# Ambiente_superior.net
KiCad netlist of a schematic drawn in EAGLE
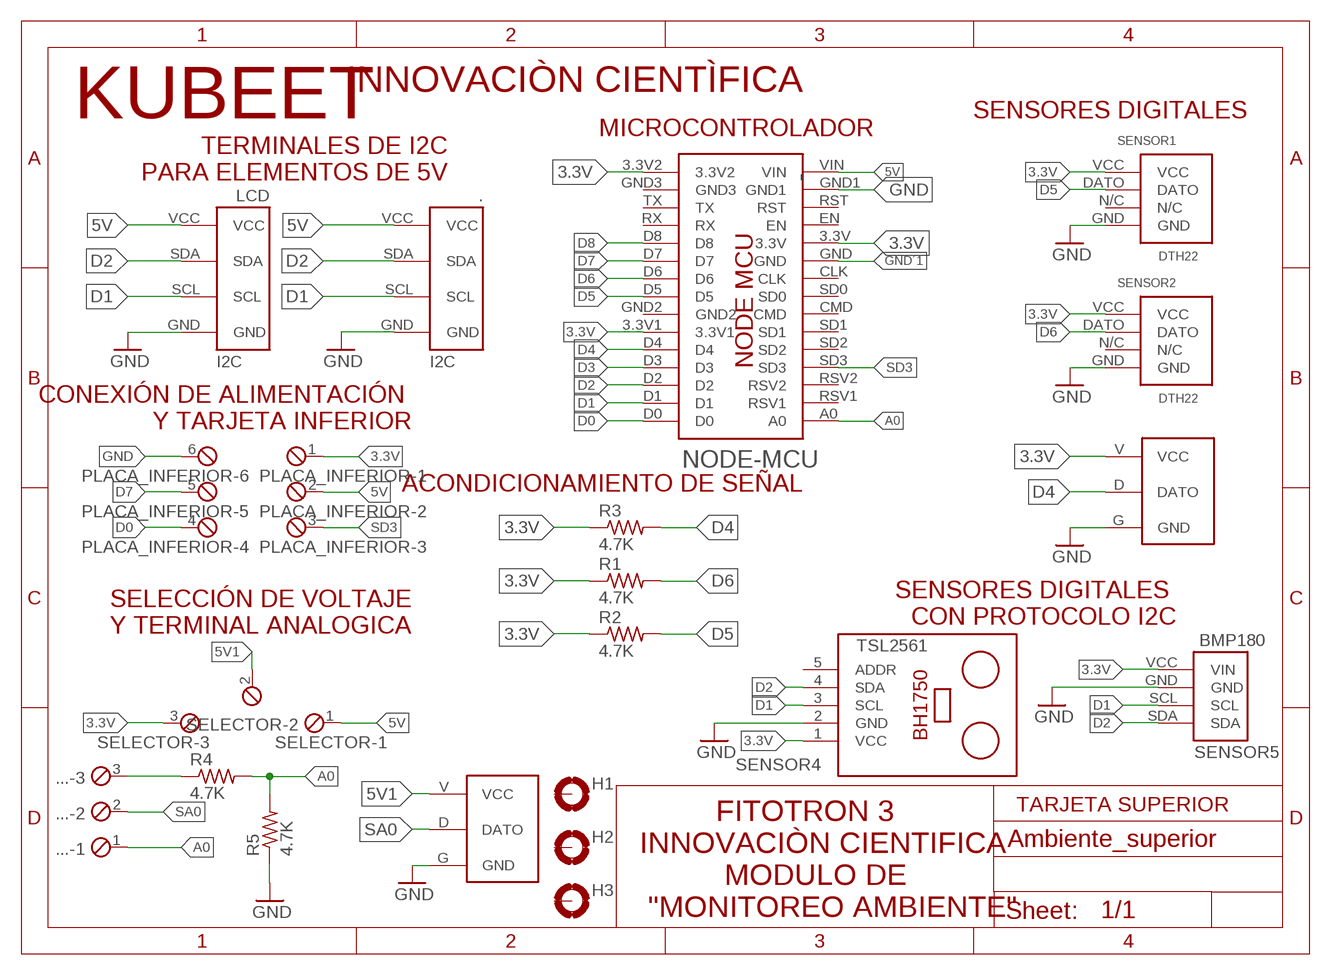
[diagram p0: schematic, sheet 1]

(export (version "E")
  (design (tool "Eeschema 10.0.6"))
  (components
    (comp (ref "-")
      (value "NODE-MCU")
      (footprint "eagle-import:NODE-MCU")
      (libsource (lib "eagle-import") (part "NODE-MCU"))
    )
    (comp (ref ".")
      (value "I2C")
      (footprint "eagle-import:I2C")
      (libsource (lib "eagle-import") (part "I2C"))
    )
    (comp (ref "..")
      (value "LM35")
      (footprint "eagle-import:LM35")
      (libsource (lib "eagle-import") (part "LM35"))
    )
    (comp (ref "...")
      (value "MPT3")
      (footprint "eagle-import:3POL254")
      (libsource (lib "eagle-import") (part "MPT3"))
    )
    (comp (ref "H1")
      (value "MOUNT-PAD-ROUND3.6")
      (footprint "eagle-import:3,6-PAD")
      (libsource (lib "eagle-import") (part "MOUNT-PAD-ROUND3.6"))
    )
    (comp (ref "H2")
      (value "MOUNT-PAD-ROUND3.6")
      (footprint "eagle-import:3,6-PAD")
      (libsource (lib "eagle-import") (part "MOUNT-PAD-ROUND3.6"))
    )
    (comp (ref "H3")
      (value "MOUNT-PAD-ROUND3.6")
      (footprint "eagle-import:3,6-PAD")
      (libsource (lib "eagle-import") (part "MOUNT-PAD-ROUND3.6"))
    )
    (comp (ref "LCD")
      (value "I2C")
      (footprint "eagle-import:I2C")
      (libsource (lib "eagle-import") (part "I2C"))
    )
    (comp (ref "PLACA_INFERIOR")
      (value "MPT6")
      (footprint "eagle-import:6POL254")
      (libsource (lib "eagle-import") (part "MPT6"))
    )
    (comp (ref "R1")
      (value "4.7K")
      (footprint "eagle-import:0207_7")
      (libsource (lib "eagle-import") (part "R-US_0207/7"))
    )
    (comp (ref "R2")
      (value "4.7K")
      (footprint "eagle-import:0207_7")
      (libsource (lib "eagle-import") (part "R-US_0207/7"))
    )
    (comp (ref "R3")
      (value "4.7K")
      (footprint "eagle-import:0207_7")
      (libsource (lib "eagle-import") (part "R-US_0207/7"))
    )
    (comp (ref "R4")
      (value "4.7K")
      (footprint "eagle-import:0207_7")
      (libsource (lib "eagle-import") (part "R-US_0207/7"))
    )
    (comp (ref "R5")
      (value "4.7K")
      (footprint "eagle-import:0207_7")
      (libsource (lib "eagle-import") (part "R-US_0207/7"))
    )
    (comp (ref "SELECTOR")
      (value "MPT3")
      (footprint "eagle-import:3POL254")
      (libsource (lib "eagle-import") (part "MPT3"))
    )
    (comp (ref "SENSOR1")
      (value "DTH22")
      (footprint "eagle-import:DTH22")
      (libsource (lib "eagle-import") (part "DTH22"))
    )
    (comp (ref "SENSOR2")
      (value "DTH22")
      (footprint "eagle-import:DTH22")
      (libsource (lib "eagle-import") (part "DTH22"))
    )
    (comp (ref "SENSOR3")
      (value "DS18B20")
      (footprint "eagle-import:LM35")
      (libsource (lib "eagle-import") (part "LM35"))
    )
    (comp (ref "SENSOR4")
      (value "TSL2561")
      (footprint "eagle-import:LIGHT-SENSOR-BH1750")
      (libsource (lib "eagle-import") (part "LIGHT-SENSOR-BH1750"))
    )
    (comp (ref "SENSOR5")
      (value "BMP180")
      (footprint "eagle-import:BMP180")
      (libsource (lib "eagle-import") (part "BMP180"))
    )
  )
  (nets
    (net (code "1") (name "3.3V") (class "Default")
      (node (ref "-") (pin "3.3V") (pinfunction "3.3V_3.3V") (pintype "bidirectional"))
      (node (ref "-") (pin "3.3V1") (pinfunction "3.3V1_3.3V1") (pintype "bidirectional"))
      (node (ref "-") (pin "3.3V2") (pinfunction "3.3V2_3.3V2") (pintype "bidirectional"))
      (node (ref "PLACA_INFERIOR") (pin "1") (pinfunction "1_1") (pintype "passive"))
      (node (ref "R1") (pin "1") (pinfunction "1_1") (pintype "passive"))
      (node (ref "R2") (pin "1") (pinfunction "1_1") (pintype "passive"))
      (node (ref "R3") (pin "1") (pinfunction "1_1") (pintype "passive"))
      (node (ref "SELECTOR") (pin "3") (pinfunction "1_3") (pintype "passive"))
      (node (ref "SENSOR1") (pin "VCC") (pinfunction "VCC_VCC") (pintype "bidirectional"))
      (node (ref "SENSOR2") (pin "VCC") (pinfunction "VCC_VCC") (pintype "bidirectional"))
      (node (ref "SENSOR3") (pin "V") (pinfunction "VCC_V") (pintype "bidirectional"))
      (node (ref "SENSOR4") (pin "1") (pinfunction "VCC_1") (pintype "power_in"))
      (node (ref "SENSOR5") (pin "VCC") (pinfunction "VIN_VCC") (pintype "bidirectional"))
    )
    (net (code "2") (name "5V") (class "Default")
      (node (ref "-") (pin "VIN") (pinfunction "VIN_VIN") (pintype "bidirectional"))
      (node (ref ".") (pin "VCC") (pinfunction "VCC_VCC") (pintype "bidirectional"))
      (node (ref "LCD") (pin "VCC") (pinfunction "VCC_VCC") (pintype "bidirectional"))
      (node (ref "PLACA_INFERIOR") (pin "2") (pinfunction "1_2") (pintype "passive"))
      (node (ref "SELECTOR") (pin "1") (pinfunction "1_1") (pintype "passive"))
    )
    (net (code "3") (name "5V1") (class "Default")
      (node (ref "..") (pin "V") (pinfunction "VCC_V") (pintype "bidirectional"))
      (node (ref "SELECTOR") (pin "2") (pinfunction "1_2") (pintype "passive"))
    )
    (net (code "4") (name "A0") (class "Default")
      (node (ref "-") (pin "A0") (pinfunction "A0_A0") (pintype "bidirectional"))
      (node (ref "...") (pin "1") (pinfunction "1_1") (pintype "passive"))
      (node (ref "R4") (pin "2") (pinfunction "2_2") (pintype "passive"))
      (node (ref "R5") (pin "2") (pinfunction "2_2") (pintype "passive"))
    )
    (net (code "5") (name "D0") (class "Default")
      (node (ref "-") (pin "D0") (pinfunction "D0_D0") (pintype "bidirectional"))
      (node (ref "PLACA_INFERIOR") (pin "4") (pinfunction "1_4") (pintype "passive"))
    )
    (net (code "6") (name "D1") (class "Default")
      (node (ref "-") (pin "D1") (pinfunction "D1_D1") (pintype "bidirectional"))
      (node (ref ".") (pin "SCL") (pinfunction "SCL_SCL") (pintype "bidirectional"))
      (node (ref "LCD") (pin "SCL") (pinfunction "SCL_SCL") (pintype "bidirectional"))
      (node (ref "SENSOR4") (pin "3") (pinfunction "SCL_3") (pintype "bidirectional"))
      (node (ref "SENSOR5") (pin "SCL") (pinfunction "SCL_SCL") (pintype "bidirectional"))
    )
    (net (code "7") (name "D2") (class "Default")
      (node (ref "-") (pin "D2") (pinfunction "D2_D2") (pintype "bidirectional"))
      (node (ref ".") (pin "SDA") (pinfunction "SDA_SDA") (pintype "bidirectional"))
      (node (ref "LCD") (pin "SDA") (pinfunction "SDA_SDA") (pintype "bidirectional"))
      (node (ref "SENSOR4") (pin "4") (pinfunction "SDA_4") (pintype "bidirectional"))
      (node (ref "SENSOR5") (pin "SDA") (pinfunction "SDA_SDA") (pintype "bidirectional"))
    )
    (net (code "8") (name "D3") (class "Default")
      (node (ref "-") (pin "D3") (pinfunction "D3_D3") (pintype "bidirectional"))
    )
    (net (code "9") (name "D4") (class "Default")
      (node (ref "-") (pin "D4") (pinfunction "D4_D4") (pintype "bidirectional"))
      (node (ref "R3") (pin "2") (pinfunction "2_2") (pintype "passive"))
      (node (ref "SENSOR3") (pin "D") (pinfunction "DATO_D") (pintype "bidirectional"))
    )
    (net (code "10") (name "D5") (class "Default")
      (node (ref "-") (pin "D5") (pinfunction "D5_D5") (pintype "bidirectional"))
      (node (ref "R2") (pin "2") (pinfunction "2_2") (pintype "passive"))
      (node (ref "SENSOR1") (pin "DATO") (pinfunction "DATO_DATO") (pintype "bidirectional"))
    )
    (net (code "11") (name "D6") (class "Default")
      (node (ref "-") (pin "D6") (pinfunction "D6_D6") (pintype "bidirectional"))
      (node (ref "R1") (pin "2") (pinfunction "2_2") (pintype "passive"))
      (node (ref "SENSOR2") (pin "DATO") (pinfunction "DATO_DATO") (pintype "bidirectional"))
    )
    (net (code "12") (name "D7") (class "Default")
      (node (ref "-") (pin "D7") (pinfunction "D7_D7") (pintype "bidirectional"))
      (node (ref "PLACA_INFERIOR") (pin "5") (pinfunction "1_5") (pintype "passive"))
    )
    (net (code "13") (name "D8") (class "Default")
      (node (ref "-") (pin "D8") (pinfunction "D8_D8") (pintype "bidirectional"))
    )
    (net (code "14") (name "GND") (class "Default")
      (node (ref "-") (pin "GND1") (pinfunction "GND1_GND1") (pintype "bidirectional"))
      (node (ref ".") (pin "GND") (pinfunction "GND_GND") (pintype "bidirectional"))
      (node (ref "..") (pin "G") (pinfunction "GND_G") (pintype "bidirectional"))
      (node (ref "LCD") (pin "GND") (pinfunction "GND_GND") (pintype "bidirectional"))
      (node (ref "PLACA_INFERIOR") (pin "6") (pinfunction "1_6") (pintype "passive"))
      (node (ref "R5") (pin "1") (pinfunction "1_1") (pintype "passive"))
      (node (ref "SENSOR1") (pin "GND") (pinfunction "GND_GND") (pintype "bidirectional"))
      (node (ref "SENSOR2") (pin "GND") (pinfunction "GND_GND") (pintype "bidirectional"))
      (node (ref "SENSOR3") (pin "G") (pinfunction "GND_G") (pintype "bidirectional"))
      (node (ref "SENSOR4") (pin "2") (pinfunction "GND_2") (pintype "power_in"))
      (node (ref "SENSOR5") (pin "GND") (pinfunction "GND_GND") (pintype "bidirectional"))
    )
    (net (code "15") (name "GND´1") (class "Default")
      (node (ref "-") (pin "GND") (pinfunction "GND_GND") (pintype "bidirectional"))
    )
    (net (code "16") (name "Net-(...C-1)") (class "Default")
      (node (ref "...") (pin "3") (pinfunction "1_3") (pintype "passive"))
      (node (ref "R4") (pin "1") (pinfunction "1_1") (pintype "passive"))
    )
    (net (code "17") (name "SA0") (class "Default")
      (node (ref "..") (pin "D") (pinfunction "DATO_D") (pintype "bidirectional"))
      (node (ref "...") (pin "2") (pinfunction "1_2") (pintype "passive"))
    )
    (net (code "18") (name "SD3") (class "Default")
      (node (ref "-") (pin "SD3") (pinfunction "SD3_SD3") (pintype "bidirectional"))
      (node (ref "PLACA_INFERIOR") (pin "3") (pinfunction "1_3") (pintype "passive"))
    )
    (net (code "19") (name "unconnected-(--PadCLK)") (class "Default")
      (node (ref "-") (pin "CLK") (pinfunction "CLK_CLK") (pintype "bidirectional"))
    )
    (net (code "20") (name "unconnected-(--PadCMD)") (class "Default")
      (node (ref "-") (pin "CMD") (pinfunction "CMD_CMD") (pintype "bidirectional"))
    )
    (net (code "21") (name "unconnected-(--PadEN)") (class "Default")
      (node (ref "-") (pin "EN") (pinfunction "EN_EN") (pintype "bidirectional"))
    )
    (net (code "22") (name "unconnected-(--PadGND2)") (class "Default")
      (node (ref "-") (pin "GND2") (pinfunction "GND2_GND2") (pintype "bidirectional"))
    )
    (net (code "23") (name "unconnected-(--PadGND3)") (class "Default")
      (node (ref "-") (pin "GND3") (pinfunction "GND3_GND3") (pintype "bidirectional"))
    )
    (net (code "24") (name "unconnected-(--PadRST)") (class "Default")
      (node (ref "-") (pin "RST") (pinfunction "RST_RST") (pintype "bidirectional"))
    )
    (net (code "25") (name "unconnected-(--PadRSV1)") (class "Default")
      (node (ref "-") (pin "RSV1") (pinfunction "RSV1_RSV1") (pintype "bidirectional"))
    )
    (net (code "26") (name "unconnected-(--PadRSV2)") (class "Default")
      (node (ref "-") (pin "RSV2") (pinfunction "RSV2_RSV2") (pintype "bidirectional"))
    )
    (net (code "27") (name "unconnected-(--PadRX)") (class "Default")
      (node (ref "-") (pin "RX") (pinfunction "RX_RX") (pintype "bidirectional"))
    )
    (net (code "28") (name "unconnected-(--PadSD0)") (class "Default")
      (node (ref "-") (pin "SD0") (pinfunction "SD0_SD0") (pintype "bidirectional"))
    )
    (net (code "29") (name "unconnected-(--PadSD1)") (class "Default")
      (node (ref "-") (pin "SD1") (pinfunction "SD1_SD1") (pintype "bidirectional"))
    )
    (net (code "30") (name "unconnected-(--PadSD2)") (class "Default")
      (node (ref "-") (pin "SD2") (pinfunction "SD2_SD2") (pintype "bidirectional"))
    )
    (net (code "31") (name "unconnected-(--PadTX)") (class "Default")
      (node (ref "-") (pin "TX") (pinfunction "TX_TX") (pintype "bidirectional"))
    )
    (net (code "32") (name "unconnected-(H1-MOUNT-PadB3,6)") (class "Default")
      (node (ref "H1") (pin "B3,6") (pinfunction "MOUNT_B3,6") (pintype "passive"))
    )
    (net (code "33") (name "unconnected-(H2-MOUNT-PadB3,6)") (class "Default")
      (node (ref "H2") (pin "B3,6") (pinfunction "MOUNT_B3,6") (pintype "passive"))
    )
    (net (code "34") (name "unconnected-(H3-MOUNT-PadB3,6)") (class "Default")
      (node (ref "H3") (pin "B3,6") (pinfunction "MOUNT_B3,6") (pintype "passive"))
    )
    (net (code "35") (name "unconnected-(SENSOR1-PadN{slash}C)") (class "Default")
      (node (ref "SENSOR1") (pin "N/C") (pinfunction "N/C_N/C") (pintype "bidirectional"))
    )
    (net (code "36") (name "unconnected-(SENSOR2-PadN{slash}C)") (class "Default")
      (node (ref "SENSOR2") (pin "N/C") (pinfunction "N/C_N/C") (pintype "bidirectional"))
    )
    (net (code "37") (name "unconnected-(SENSOR4-ADDR-Pad5)") (class "Default")
      (node (ref "SENSOR4") (pin "5") (pinfunction "ADDR_5") (pintype "bidirectional"))
    )
  )
)
